# JTAG_Configuration.net
KiCad netlist of a schematic drawn in Altium Designer
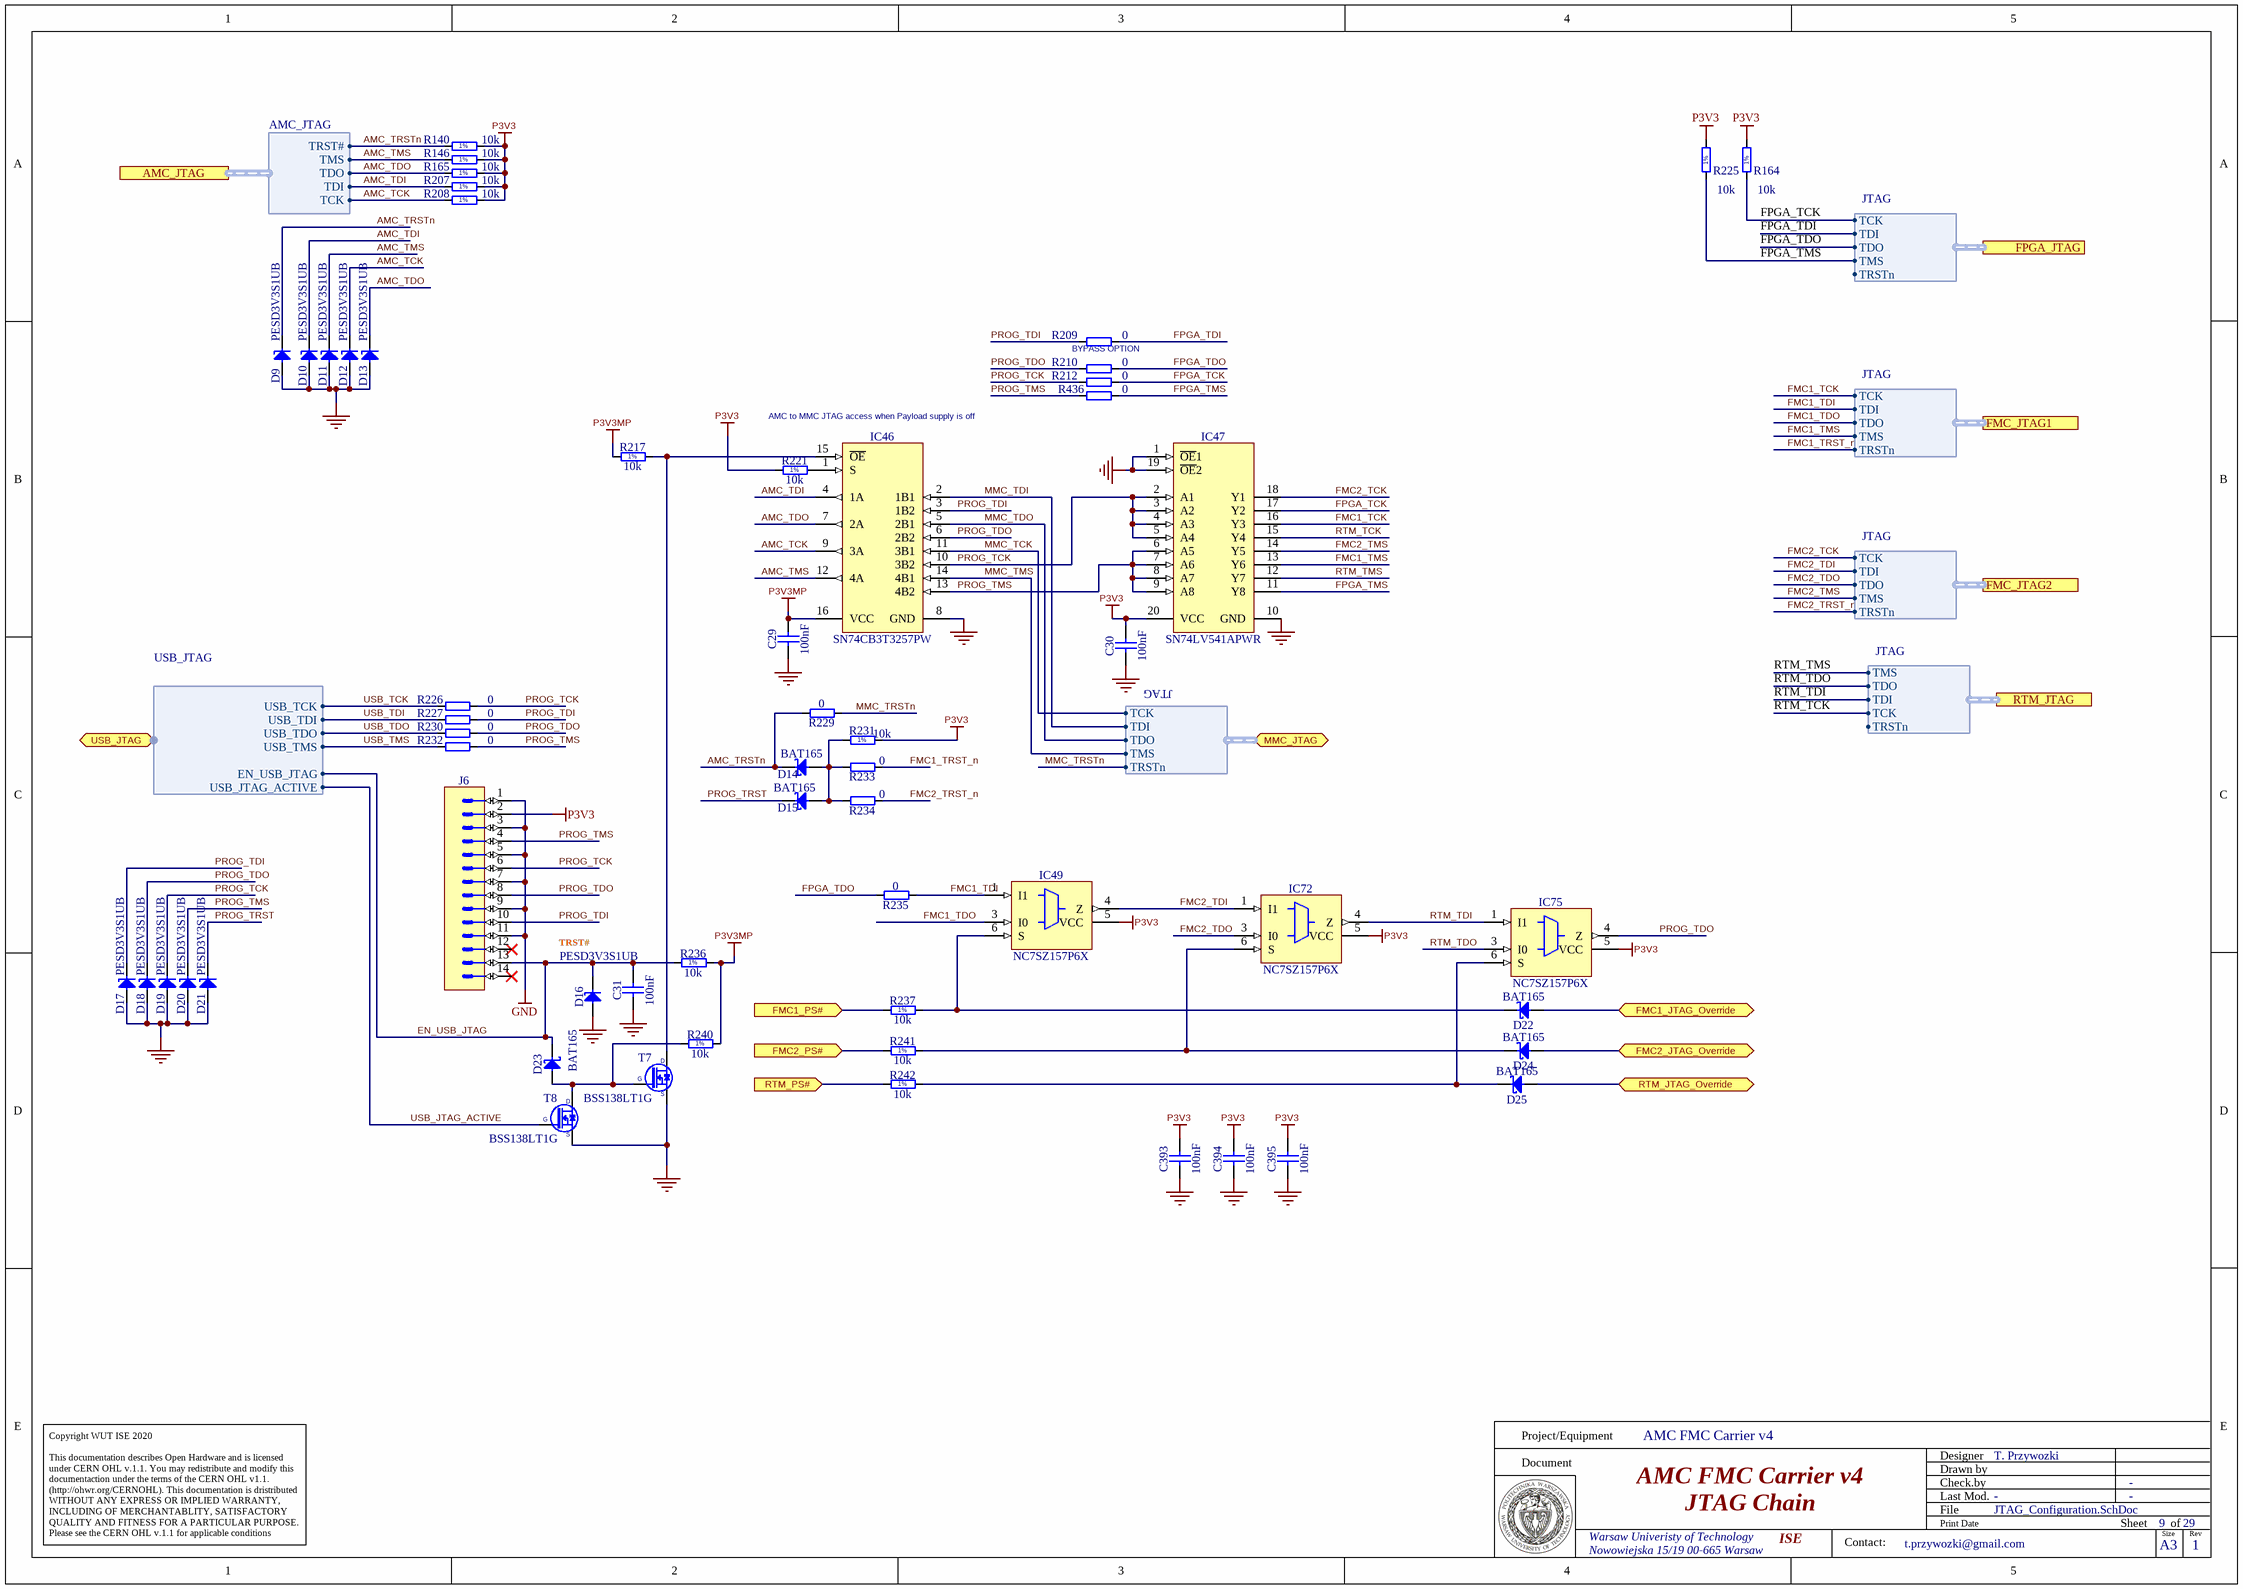
[diagram p0: JTAG_Configuration.SchDoc]

(export (version "E")
  (design (tool "Eeschema 10.0.6"))
  (components
    (comp (ref "C29")
      (value "100nF")
      (footprint "CAPC0603X33N")
      (description "Non-polarised capacitor")
      (fields
        (field (name "MANUFACTURER PART NUMBER") "CC0201_100NF_6.3V_10%_X5R")
        (field (name "MANUFACTURER") "GENERIC")
        (field (name "AUTHOR") "CERN DEM JLC")
      )
      (libsource (lib "Capacitors") (part "Capacitor - non polarized"))
    )
    (comp (ref "C30")
      (value "100nF")
      (footprint "CAPC0603X33N")
      (description "Non-polarised capacitor")
      (fields
        (field (name "MANUFACTURER PART NUMBER") "CC0201_100NF_6.3V_10%_X5R")
        (field (name "MANUFACTURER") "GENERIC")
        (field (name "AUTHOR") "CERN DEM JLC")
      )
      (libsource (lib "Capacitors") (part "Capacitor - non polarized"))
    )
    (comp (ref "C31")
      (value "100nF")
      (footprint "CAPC0603X33N")
      (description "Non-polarised capacitor")
      (fields
        (field (name "MANUFACTURER PART NUMBER") "CC0201_100NF_6.3V_10%_X5R")
        (field (name "MANUFACTURER") "GENERIC")
        (field (name "AUTHOR") "CERN DEM JLC")
      )
      (libsource (lib "Capacitors") (part "Capacitor - non polarized"))
    )
    (comp (ref "C393")
      (value "100nF")
      (footprint "CAPC0603X33N")
      (description "Non-polarised capacitor")
      (fields
        (field (name "MANUFACTURER PART NUMBER") "CC0201_100NF_6.3V_10%_X5R")
        (field (name "MANUFACTURER") "GENERIC")
        (field (name "AUTHOR") "CERN DEM JLC")
      )
      (libsource (lib "Capacitors") (part "Capacitor - non polarized"))
    )
    (comp (ref "C394")
      (value "100nF")
      (footprint "CAPC0603X33N")
      (description "Non-polarised capacitor")
      (fields
        (field (name "MANUFACTURER PART NUMBER") "CC0201_100NF_6.3V_10%_X5R")
        (field (name "MANUFACTURER") "GENERIC")
        (field (name "AUTHOR") "CERN DEM JLC")
      )
      (libsource (lib "Capacitors") (part "Capacitor - non polarized"))
    )
    (comp (ref "C395")
      (value "100nF")
      (footprint "CAPC0603X33N")
      (description "Non-polarised capacitor")
      (fields
        (field (name "MANUFACTURER PART NUMBER") "CC0201_100NF_6.3V_10%_X5R")
        (field (name "MANUFACTURER") "GENERIC")
        (field (name "AUTHOR") "CERN DEM JLC")
      )
      (libsource (lib "Capacitors") (part "Capacitor - non polarized"))
    )
    (comp (ref "D9")
      (value "PESD3V3S1UB")
      (footprint "SODFL1608X65N")
      (description "ESD protection diode")
      (fields
        (field (name "MANUFACTURER") "NXP SEMICONDUCTORS")
        (field (name "VOLTAGE") "3V3")
        (field (name "AUTHOR") "CERN DEM JLC")
      )
      (libsource (lib "ICs And Semiconductors") (part "Diode ESD"))
    )
    (comp (ref "D10")
      (value "PESD3V3S1UB")
      (footprint "SODFL1608X65N")
      (description "ESD protection diode")
      (fields
        (field (name "MANUFACTURER") "NXP SEMICONDUCTORS")
        (field (name "VOLTAGE") "3V3")
        (field (name "AUTHOR") "CERN DEM JLC")
      )
      (libsource (lib "ICs And Semiconductors") (part "Diode ESD"))
    )
    (comp (ref "D11")
      (value "PESD3V3S1UB")
      (footprint "SODFL1608X65N")
      (description "ESD protection diode")
      (fields
        (field (name "MANUFACTURER") "NXP SEMICONDUCTORS")
        (field (name "VOLTAGE") "3V3")
        (field (name "AUTHOR") "CERN DEM JLC")
      )
      (libsource (lib "ICs And Semiconductors") (part "Diode ESD"))
    )
    (comp (ref "D12")
      (value "PESD3V3S1UB")
      (footprint "SODFL1608X65N")
      (description "ESD protection diode")
      (fields
        (field (name "MANUFACTURER") "NXP SEMICONDUCTORS")
        (field (name "VOLTAGE") "3V3")
        (field (name "AUTHOR") "CERN DEM JLC")
      )
      (libsource (lib "ICs And Semiconductors") (part "Diode ESD"))
    )
    (comp (ref "D13")
      (value "PESD3V3S1UB")
      (footprint "SODFL1608X65N")
      (description "ESD protection diode")
      (fields
        (field (name "MANUFACTURER") "NXP SEMICONDUCTORS")
        (field (name "VOLTAGE") "3V3")
        (field (name "AUTHOR") "CERN DEM JLC")
      )
      (libsource (lib "ICs And Semiconductors") (part "Diode ESD"))
    )
    (comp (ref "D14")
      (value "BAT165")
      (footprint "SOD2512X110N")
      (description "Schottky Diode")
      (fields
        (field (name "MANUFACTURER") "INFINEON")
        (field (name "VOLTAGE") "40V")
        (field (name "AUTHOR") "CERN DEM JLC")
      )
      (libsource (lib "ICs And Semiconductors") (part "Diode Schottky"))
    )
    (comp (ref "D15")
      (value "BAT165")
      (footprint "SOD2512X110N")
      (description "Schottky Diode")
      (fields
        (field (name "MANUFACTURER") "INFINEON")
        (field (name "VOLTAGE") "40V")
        (field (name "AUTHOR") "CERN DEM JLC")
      )
      (libsource (lib "ICs And Semiconductors") (part "Diode Schottky"))
    )
    (comp (ref "D16")
      (value "PESD3V3S1UB")
      (footprint "SODFL1608X65N")
      (description "ESD protection diode")
      (fields
        (field (name "MANUFACTURER") "NXP SEMICONDUCTORS")
        (field (name "VOLTAGE") "3V3")
        (field (name "AUTHOR") "CERN DEM JLC")
      )
      (libsource (lib "ICs And Semiconductors") (part "Diode ESD"))
    )
    (comp (ref "D17")
      (value "PESD3V3S1UB")
      (footprint "SODFL1608X65N")
      (description "ESD protection diode")
      (fields
        (field (name "MANUFACTURER") "NXP SEMICONDUCTORS")
        (field (name "VOLTAGE") "3V3")
        (field (name "AUTHOR") "CERN DEM JLC")
      )
      (libsource (lib "ICs And Semiconductors") (part "Diode ESD"))
    )
    (comp (ref "D18")
      (value "PESD3V3S1UB")
      (footprint "SODFL1608X65N")
      (description "ESD protection diode")
      (fields
        (field (name "MANUFACTURER") "NXP SEMICONDUCTORS")
        (field (name "VOLTAGE") "3V3")
        (field (name "AUTHOR") "CERN DEM JLC")
      )
      (libsource (lib "ICs And Semiconductors") (part "Diode ESD"))
    )
    (comp (ref "D19")
      (value "PESD3V3S1UB")
      (footprint "SODFL1608X65N")
      (description "ESD protection diode")
      (fields
        (field (name "MANUFACTURER") "NXP SEMICONDUCTORS")
        (field (name "VOLTAGE") "3V3")
        (field (name "AUTHOR") "CERN DEM JLC")
      )
      (libsource (lib "ICs And Semiconductors") (part "Diode ESD"))
    )
    (comp (ref "D20")
      (value "PESD3V3S1UB")
      (footprint "SODFL1608X65N")
      (description "ESD protection diode")
      (fields
        (field (name "MANUFACTURER") "NXP SEMICONDUCTORS")
        (field (name "VOLTAGE") "3V3")
        (field (name "AUTHOR") "CERN DEM JLC")
      )
      (libsource (lib "ICs And Semiconductors") (part "Diode ESD"))
    )
    (comp (ref "D21")
      (value "PESD3V3S1UB")
      (footprint "SODFL1608X65N")
      (description "ESD protection diode")
      (fields
        (field (name "MANUFACTURER") "NXP SEMICONDUCTORS")
        (field (name "VOLTAGE") "3V3")
        (field (name "AUTHOR") "CERN DEM JLC")
      )
      (libsource (lib "ICs And Semiconductors") (part "Diode ESD"))
    )
    (comp (ref "D22")
      (value "BAT165")
      (footprint "SOD2512X110N")
      (description "Schottky Diode")
      (fields
        (field (name "MANUFACTURER") "INFINEON")
        (field (name "VOLTAGE") "40V")
        (field (name "AUTHOR") "CERN DEM JLC")
      )
      (libsource (lib "ICs And Semiconductors") (part "Diode Schottky"))
    )
    (comp (ref "D23")
      (value "BAT165")
      (footprint "SOD2512X110N")
      (description "Schottky Diode")
      (fields
        (field (name "MANUFACTURER") "INFINEON")
        (field (name "VOLTAGE") "40V")
        (field (name "AUTHOR") "CERN DEM JLC")
      )
      (libsource (lib "ICs And Semiconductors") (part "Diode Schottky"))
    )
    (comp (ref "D24")
      (value "BAT165")
      (footprint "SOD2512X110N")
      (description "Schottky Diode")
      (fields
        (field (name "MANUFACTURER") "INFINEON")
        (field (name "VOLTAGE") "40V")
        (field (name "AUTHOR") "CERN DEM JLC")
      )
      (libsource (lib "ICs And Semiconductors") (part "Diode Schottky"))
    )
    (comp (ref "D25")
      (value "BAT165")
      (footprint "SOD2512X110N")
      (description "Schottky Diode")
      (fields
        (field (name "MANUFACTURER") "INFINEON")
        (field (name "VOLTAGE") "40V")
        (field (name "AUTHOR") "CERN DEM JLC")
      )
      (libsource (lib "ICs And Semiconductors") (part "Diode Schottky"))
    )
    (comp (ref "IC46")
      (value "SN74CB3T3257PW")
      (footprint "SOP65P640X120-16N")
      (description "4-BIT 1-OF-2 FET Multiplexer/Demultiplexer 2.5V/3.3V Low-Voltage Bus Switch 5V Tolerant Shifter")
      (fields (field (name "MANUFACTURER") "TEXAS INSTRUMENTS") (field (name "AUTHOR") "CERN DEM JLC"))
      (libsource (lib "ICs And Semiconductors") (part "743257"))
    )
    (comp (ref "IC47")
      (value "SN74LV541APWR")
      (footprint "SOP65P640X120-20N")
      (description "Octal Buffer/Line Driver with 3-State Outputs")
      (fields (field (name "MANUFACTURER") "TEXAS INSTRUMENTS") (field (name "AUTHOR") "CERN DEM JLC"))
      (libsource (lib "ICs And Semiconductors") (part "74541"))
    )
    (comp (ref "IC49")
      (value "NC7SZ157P6X")
      (footprint "SOT65P210X110-6N")
      (description "TinyLogic® UHS 2-Input Non-Inverting Multiplexer")
      (fields (field (name "MANUFACTURER") "FAIRCHILD SEMICONDUCTOR") (field (name "AUTHOR") "CERN DEM JLC"))
      (libsource (lib "ICs And Semiconductors") (part "NC7SZ157"))
    )
    (comp (ref "IC72")
      (value "NC7SZ157P6X")
      (footprint "SOT65P210X110-6N")
      (description "TinyLogic® UHS 2-Input Non-Inverting Multiplexer")
      (fields (field (name "MANUFACTURER") "FAIRCHILD SEMICONDUCTOR") (field (name "AUTHOR") "CERN DEM JLC"))
      (libsource (lib "ICs And Semiconductors") (part "NC7SZ157"))
    )
    (comp (ref "IC75")
      (value "NC7SZ157P6X")
      (footprint "SOT65P210X110-6N")
      (description "TinyLogic® UHS 2-Input Non-Inverting Multiplexer")
      (fields (field (name "MANUFACTURER") "FAIRCHILD SEMICONDUCTOR") (field (name "AUTHOR") "CERN DEM JLC"))
      (libsource (lib "ICs And Semiconductors") (part "NC7SZ157"))
    )
    (comp (ref "J6")
      (value "Milli-Grid™")
      (footprint "MOLEX_87832-1420")
      (description "Connector 14 Male")
      (fields
        (field (name "PART NUMBER") "MOLEX_87832-1420")
        (field (name "MANUFACTURER") "MOLEX")
        (field (name "AUTHOR") "CERN DEM JLC")
      )
      (libsource (lib "Connectors") (part "Connector 14 Male"))
    )
    (comp (ref "R140")
      (value "10k")
      (footprint "RESC1005X40N")
      (description "Resistor - 1%")
      (fields
        (field (name "MANUFACTURER PART NUMBER") "R0402_10K_1%_0.0625W_100PPM")
        (field (name "MANUFACTURER") "GENERIC")
        (field (name "AUTHOR") "CERN DEM JLC")
      )
      (libsource (lib "Resistors") (part "Resistor - 1%"))
    )
    (comp (ref "R146")
      (value "10k")
      (footprint "RESC1005X40N")
      (description "Resistor - 1%")
      (fields
        (field (name "MANUFACTURER PART NUMBER") "R0402_10K_1%_0.0625W_100PPM")
        (field (name "MANUFACTURER") "GENERIC")
        (field (name "AUTHOR") "CERN DEM JLC")
      )
      (libsource (lib "Resistors") (part "Resistor - 1%"))
    )
    (comp (ref "R164")
      (value "10k")
      (footprint "RESC1005X40N")
      (description "Resistor - 1%")
      (fields
        (field (name "PART NUMBER") "R0402_10K_1%_0.0625W_100PPM")
        (field (name "POWER") "0.0625W")
        (field (name "AUTHOR") "CERN DEM JLC")
      )
      (libsource (lib "Resistors") (part "Resistor - 1%"))
    )
    (comp (ref "R165")
      (value "10k")
      (footprint "RESC1005X40N")
      (description "Resistor - 1%")
      (fields
        (field (name "MANUFACTURER PART NUMBER") "R0402_10K_1%_0.0625W_100PPM")
        (field (name "MANUFACTURER") "GENERIC")
        (field (name "AUTHOR") "CERN DEM JLC")
      )
      (libsource (lib "Resistors") (part "Resistor - 1%"))
    )
    (comp (ref "R207")
      (value "10k")
      (footprint "RESC1005X40N")
      (description "Resistor - 1%")
      (fields
        (field (name "MANUFACTURER PART NUMBER") "R0402_10K_1%_0.0625W_100PPM")
        (field (name "MANUFACTURER") "GENERIC")
        (field (name "AUTHOR") "CERN DEM JLC")
      )
      (libsource (lib "Resistors") (part "Resistor - 1%"))
    )
    (comp (ref "R208")
      (value "10k")
      (footprint "RESC1005X40N")
      (description "Resistor - 1%")
      (fields
        (field (name "MANUFACTURER PART NUMBER") "R0402_10K_1%_0.0625W_100PPM")
        (field (name "MANUFACTURER") "GENERIC")
        (field (name "AUTHOR") "CERN DEM JLC")
      )
      (libsource (lib "Resistors") (part "Resistor - 1%"))
    )
    (comp (ref "R209")
      (value "0")
      (footprint "RESC1005X40N")
      (description "Resistor")
      (fields
        (field (name "MANUFACTURER PART NUMBER") "R0402_0R_JUMPER")
        (field (name "MANUFACTURER") "GENERIC")
        (field (name "AUTHOR") "CERN DEM JLC")
      )
      (libsource (lib "Resistors") (part "Resistor"))
    )
    (comp (ref "R210")
      (value "0")
      (footprint "RESC1005X40N")
      (description "Resistor")
      (fields
        (field (name "MANUFACTURER PART NUMBER") "R0402_0R_JUMPER")
        (field (name "MANUFACTURER") "GENERIC")
        (field (name "AUTHOR") "CERN DEM JLC")
      )
      (libsource (lib "Resistors") (part "Resistor"))
    )
    (comp (ref "R212")
      (value "0")
      (footprint "RESC1005X40N")
      (description "Resistor")
      (fields
        (field (name "MANUFACTURER PART NUMBER") "R0402_0R_JUMPER")
        (field (name "MANUFACTURER") "GENERIC")
        (field (name "AUTHOR") "CERN DEM JLC")
      )
      (libsource (lib "Resistors") (part "Resistor"))
    )
    (comp (ref "R217")
      (value "10k")
      (footprint "RESC1005X40N")
      (description "Resistor - 1%")
      (fields
        (field (name "MANUFACTURER PART NUMBER") "R0402_10K_1%_0.0625W_100PPM")
        (field (name "MANUFACTURER") "GENERIC")
        (field (name "AUTHOR") "CERN DEM JLC")
      )
      (libsource (lib "Resistors") (part "Resistor - 1%"))
    )
    (comp (ref "R221")
      (value "10k")
      (footprint "RESC1005X40N")
      (description "Resistor - 1%")
      (fields
        (field (name "MANUFACTURER PART NUMBER") "R0402_10K_1%_0.0625W_100PPM")
        (field (name "MANUFACTURER") "GENERIC")
        (field (name "AUTHOR") "CERN DEM JLC")
      )
      (libsource (lib "Resistors") (part "Resistor - 1%"))
    )
    (comp (ref "R225")
      (value "10k")
      (footprint "RESC1005X40N")
      (description "Resistor - 1%")
      (fields
        (field (name "PART NUMBER") "R0402_10K_1%_0.0625W_100PPM")
        (field (name "POWER") "0.0625W")
        (field (name "AUTHOR") "CERN DEM JLC")
      )
      (libsource (lib "Resistors") (part "Resistor - 1%"))
    )
    (comp (ref "R226")
      (value "0")
      (footprint "RESC1005X40N")
      (description "Resistor")
      (fields
        (field (name "MANUFACTURER PART NUMBER") "R0402_0R_JUMPER")
        (field (name "MANUFACTURER") "GENERIC")
        (field (name "AUTHOR") "CERN DEM JLC")
      )
      (libsource (lib "Resistors") (part "Resistor"))
    )
    (comp (ref "R227")
      (value "0")
      (footprint "RESC1005X40N")
      (description "Resistor")
      (fields
        (field (name "MANUFACTURER PART NUMBER") "R0402_0R_JUMPER")
        (field (name "MANUFACTURER") "GENERIC")
        (field (name "AUTHOR") "CERN DEM JLC")
      )
      (libsource (lib "Resistors") (part "Resistor"))
    )
    (comp (ref "R229")
      (value "0")
      (footprint "RESC1005X40N")
      (description "Resistor")
      (fields
        (field (name "MANUFACTURER PART NUMBER") "R0402_0R_JUMPER")
        (field (name "MANUFACTURER") "GENERIC")
        (field (name "AUTHOR") "CERN DEM JLC")
      )
      (libsource (lib "Resistors") (part "Resistor"))
    )
    (comp (ref "R230")
      (value "0")
      (footprint "RESC1005X40N")
      (description "Resistor")
      (fields
        (field (name "MANUFACTURER PART NUMBER") "R0402_0R_JUMPER")
        (field (name "MANUFACTURER") "GENERIC")
        (field (name "AUTHOR") "CERN DEM JLC")
      )
      (libsource (lib "Resistors") (part "Resistor"))
    )
    (comp (ref "R231")
      (value "10k")
      (footprint "RESC1005X40N")
      (description "Resistor - 1%")
      (fields
        (field (name "MANUFACTURER PART NUMBER") "R0402_10K_1%_0.0625W_100PPM")
        (field (name "MANUFACTURER") "GENERIC")
        (field (name "AUTHOR") "CERN DEM JLC")
      )
      (libsource (lib "Resistors") (part "Resistor - 1%"))
    )
    (comp (ref "R232")
      (value "0")
      (footprint "RESC1005X40N")
      (description "Resistor")
      (fields
        (field (name "MANUFACTURER PART NUMBER") "R0402_0R_JUMPER")
        (field (name "MANUFACTURER") "GENERIC")
        (field (name "AUTHOR") "CERN DEM JLC")
      )
      (libsource (lib "Resistors") (part "Resistor"))
    )
    (comp (ref "R233")
      (value "0")
      (footprint "RESC1005X40N")
      (description "Resistor")
      (fields
        (field (name "MANUFACTURER PART NUMBER") "R0402_0R_JUMPER")
        (field (name "MANUFACTURER") "GENERIC")
        (field (name "AUTHOR") "CERN DEM JLC")
      )
      (libsource (lib "Resistors") (part "Resistor"))
    )
    (comp (ref "R234")
      (value "0")
      (footprint "RESC1005X40N")
      (description "Resistor")
      (fields
        (field (name "MANUFACTURER PART NUMBER") "R0402_0R_JUMPER")
        (field (name "MANUFACTURER") "GENERIC")
        (field (name "AUTHOR") "CERN DEM JLC")
      )
      (libsource (lib "Resistors") (part "Resistor"))
    )
    (comp (ref "R235")
      (value "0")
      (footprint "RESC1005X40N")
      (description "Resistor")
      (fields
        (field (name "MANUFACTURER PART NUMBER") "R0402_0R_JUMPER")
        (field (name "MANUFACTURER") "GENERIC")
        (field (name "AUTHOR") "CERN DEM JLC")
      )
      (libsource (lib "Resistors") (part "Resistor"))
    )
    (comp (ref "R236")
      (value "10k")
      (footprint "RESC1005X40N")
      (description "Resistor - 1%")
      (fields
        (field (name "MANUFACTURER PART NUMBER") "R0402_10K_1%_0.0625W_100PPM")
        (field (name "MANUFACTURER") "GENERIC")
        (field (name "AUTHOR") "CERN DEM JLC")
      )
      (libsource (lib "Resistors") (part "Resistor - 1%"))
    )
    (comp (ref "R237")
      (value "10k")
      (footprint "RESC1005X40N")
      (description "Resistor - 1%")
      (fields
        (field (name "MANUFACTURER PART NUMBER") "R0402_10K_1%_0.0625W_100PPM")
        (field (name "MANUFACTURER") "GENERIC")
        (field (name "AUTHOR") "CERN DEM JLC")
      )
      (libsource (lib "Resistors") (part "Resistor - 1%"))
    )
    (comp (ref "R240")
      (value "10k")
      (footprint "RESC1005X40N")
      (description "Resistor - 1%")
      (fields
        (field (name "MANUFACTURER PART NUMBER") "R0402_10K_1%_0.0625W_100PPM")
        (field (name "MANUFACTURER") "GENERIC")
        (field (name "AUTHOR") "CERN DEM JLC")
      )
      (libsource (lib "Resistors") (part "Resistor - 1%"))
    )
    (comp (ref "R241")
      (value "10k")
      (footprint "RESC1005X40N")
      (description "Resistor - 1%")
      (fields
        (field (name "MANUFACTURER PART NUMBER") "R0402_10K_1%_0.0625W_100PPM")
        (field (name "MANUFACTURER") "GENERIC")
        (field (name "AUTHOR") "CERN DEM JLC")
      )
      (libsource (lib "Resistors") (part "Resistor - 1%"))
    )
    (comp (ref "R242")
      (value "10k")
      (footprint "RESC1005X40N")
      (description "Resistor - 1%")
      (fields
        (field (name "MANUFACTURER PART NUMBER") "R0402_10K_1%_0.0625W_100PPM")
        (field (name "MANUFACTURER") "GENERIC")
        (field (name "AUTHOR") "CERN DEM JLC")
      )
      (libsource (lib "Resistors") (part "Resistor - 1%"))
    )
    (comp (ref "R436")
      (value "0")
      (footprint "RESC1005X40N")
      (description "Resistor")
      (fields
        (field (name "MANUFACTURER PART NUMBER") "R0402_0R_JUMPER")
        (field (name "MANUFACTURER") "GENERIC")
        (field (name "AUTHOR") "CERN DEM JLC")
      )
      (libsource (lib "Resistors") (part "Resistor"))
    )
    (comp (ref "T7")
      (value "BSS138LT1G")
      (footprint "SOT95P240X110-3N")
      (description "N-CHANNEL MOSFET WITH DIODE")
      (fields (field (name "MANUFACTURER") "ON SEMICONDUCTOR") (field (name "AUTHOR") "CERN DEM JLC"))
      (libsource (lib "ICs And Semiconductors") (part "N-MOSFET-D 1G 2S 3D"))
    )
    (comp (ref "T8")
      (value "BSS138LT1G")
      (footprint "SOT95P240X110-3N")
      (description "N-CHANNEL MOSFET WITH DIODE")
      (fields (field (name "MANUFACTURER") "ON SEMICONDUCTOR") (field (name "AUTHOR") "CERN DEM JLC"))
      (libsource (lib "ICs And Semiconductors") (part "N-MOSFET-D 1G 2S 3D"))
    )
  )
  (nets
    (net (code "4") (name "/AMC_TCK") (class "Default")
      (node (ref "D12") (pin "1") (pinfunction "C_1") (pintype "passive"))
      (node (ref "IC46") (pin "9") (pinfunction "3A_9") (pintype "output"))
      (node (ref "R208") (pin "2") (pinfunction "2_2") (pintype "passive"))
    )
    (net (code "5") (name "/AMC_TDI") (class "Default")
      (node (ref "D10") (pin "1") (pinfunction "C_1") (pintype "passive"))
      (node (ref "IC46") (pin "4") (pinfunction "1A_4") (pintype "output"))
      (node (ref "R207") (pin "2") (pinfunction "2_2") (pintype "passive"))
    )
    (net (code "6") (name "/AMC_TDO") (class "Default")
      (node (ref "D13") (pin "1") (pinfunction "C_1") (pintype "passive"))
      (node (ref "IC46") (pin "7") (pinfunction "2A_7") (pintype "output"))
      (node (ref "R165") (pin "2") (pinfunction "2_2") (pintype "passive"))
    )
    (net (code "7") (name "/AMC_TMS") (class "Default")
      (node (ref "D11") (pin "1") (pinfunction "C_1") (pintype "passive"))
      (node (ref "IC46") (pin "12") (pinfunction "4A_12") (pintype "output"))
      (node (ref "R146") (pin "2") (pinfunction "2_2") (pintype "passive"))
    )
    (net (code "8") (name "/AMC_TRSTn") (class "Default")
      (node (ref "D14") (pin "1") (pinfunction "C_1") (pintype "passive"))
      (node (ref "D9") (pin "1") (pinfunction "C_1") (pintype "passive"))
      (node (ref "R140") (pin "2") (pinfunction "2_2") (pintype "passive"))
      (node (ref "R229") (pin "2") (pinfunction "2_2") (pintype "passive"))
    )
    (net (code "9") (name "/EN_USB_JTAG") (class "Default")
      (node (ref "C31") (pin "2") (pinfunction "2_2") (pintype "passive"))
      (node (ref "D16") (pin "1") (pinfunction "C_1") (pintype "passive"))
      (node (ref "D23") (pin "1") (pinfunction "C_1") (pintype "passive"))
      (node (ref "J6") (pin "13") (pinfunction "13_13") (pintype "bidirectional"))
      (node (ref "R236") (pin "1") (pinfunction "1_1") (pintype "passive"))
    )
    (net (code "10") (name "/FMC1_JTAG_Override") (class "Default")
      (node (ref "D22") (pin "2") (pinfunction "A_2") (pintype "passive"))
    )
    (net (code "11") (name "/FMC1_PS#") (class "Default")
      (node (ref "R237") (pin "2") (pinfunction "2_2") (pintype "passive"))
    )
    (net (code "12") (name "/FMC1_TCK") (class "Default")
      (node (ref "IC47") (pin "16") (pinfunction "Y3_16") (pintype "tri_state"))
    )
    (net (code "13") (name "/FMC1_TDI") (class "Default")
      (node (ref "IC49") (pin "1") (pinfunction "I1_1") (pintype "input"))
      (node (ref "R235") (pin "1") (pinfunction "1_1") (pintype "passive"))
    )
    (net (code "14") (name "/FMC1_TDO") (class "Default")
      (node (ref "IC49") (pin "3") (pinfunction "I0_3") (pintype "input"))
    )
    (net (code "15") (name "/FMC1_TMS") (class "Default")
      (node (ref "IC47") (pin "13") (pinfunction "Y6_13") (pintype "tri_state"))
    )
    (net (code "16") (name "/FMC1_TRST_n") (class "Default")
      (node (ref "R233") (pin "1") (pinfunction "1_1") (pintype "passive"))
    )
    (net (code "17") (name "/FMC2_JTAG_Override") (class "Default")
      (node (ref "D24") (pin "2") (pinfunction "A_2") (pintype "passive"))
    )
    (net (code "18") (name "/FMC2_PS#") (class "Default")
      (node (ref "R241") (pin "2") (pinfunction "2_2") (pintype "passive"))
    )
    (net (code "19") (name "/FMC2_TCK") (class "Default")
      (node (ref "IC47") (pin "18") (pinfunction "Y1_18") (pintype "tri_state"))
    )
    (net (code "20") (name "/FMC2_TDI") (class "Default")
      (node (ref "IC49") (pin "4") (pinfunction "Z_4") (pintype "output"))
      (node (ref "IC72") (pin "1") (pinfunction "I1_1") (pintype "input"))
    )
    (net (code "21") (name "/FMC2_TDO") (class "Default")
      (node (ref "IC72") (pin "3") (pinfunction "I0_3") (pintype "input"))
    )
    (net (code "22") (name "/FMC2_TMS") (class "Default")
      (node (ref "IC47") (pin "14") (pinfunction "Y5_14") (pintype "tri_state"))
    )
    (net (code "23") (name "/FMC2_TRST_n") (class "Default")
      (node (ref "R234") (pin "1") (pinfunction "1_1") (pintype "passive"))
    )
    (net (code "24") (name "/FPGA_TCK") (class "Default")
      (node (ref "IC47") (pin "17") (pinfunction "Y2_17") (pintype "tri_state"))
      (node (ref "R164") (pin "1") (pinfunction "1_1") (pintype "passive"))
      (node (ref "R212") (pin "1") (pinfunction "1_1") (pintype "passive"))
    )
    (net (code "25") (name "/FPGA_TDI") (class "Default")
      (node (ref "R209") (pin "1") (pinfunction "1_1") (pintype "passive"))
    )
    (net (code "26") (name "/FPGA_TDO") (class "Default")
      (node (ref "R210") (pin "1") (pinfunction "1_1") (pintype "passive"))
      (node (ref "R235") (pin "2") (pinfunction "2_2") (pintype "passive"))
    )
    (net (code "27") (name "/FPGA_TMS") (class "Default")
      (node (ref "IC47") (pin "11") (pinfunction "Y8_11") (pintype "tri_state"))
      (node (ref "R225") (pin "1") (pinfunction "1_1") (pintype "passive"))
      (node (ref "R436") (pin "1") (pinfunction "1_1") (pintype "passive"))
    )
    (net (code "28") (name "/MMC_TCK") (class "Default")
      (node (ref "IC46") (pin "11") (pinfunction "3B1_11") (pintype "input"))
    )
    (net (code "29") (name "/MMC_TDI") (class "Default")
      (node (ref "IC46") (pin "2") (pinfunction "1B1_2") (pintype "input"))
    )
    (net (code "30") (name "/MMC_TDO") (class "Default")
      (node (ref "IC46") (pin "5") (pinfunction "2B1_5") (pintype "input"))
    )
    (net (code "31") (name "/MMC_TMS") (class "Default")
      (node (ref "IC46") (pin "14") (pinfunction "4B1_14") (pintype "input"))
    )
    (net (code "32") (name "/MMC_TRSTn") (class "Default")
      (node (ref "R229") (pin "1") (pinfunction "1_1") (pintype "passive"))
    )
    (net (code "33") (name "/PROG_TCK") (class "Default")
      (node (ref "D19") (pin "1") (pinfunction "C_1") (pintype "passive"))
      (node (ref "IC46") (pin "10") (pinfunction "3B2_10") (pintype "input"))
      (node (ref "IC47") (pin "2") (pinfunction "A1_2") (pintype "input"))
      (node (ref "IC47") (pin "3") (pinfunction "A2_3") (pintype "input"))
      (node (ref "IC47") (pin "4") (pinfunction "A3_4") (pintype "input"))
      (node (ref "IC47") (pin "5") (pinfunction "A4_5") (pintype "input"))
      (node (ref "J6") (pin "6") (pinfunction "6_6") (pintype "bidirectional"))
      (node (ref "R212") (pin "2") (pinfunction "2_2") (pintype "passive"))
      (node (ref "R226") (pin "1") (pinfunction "1_1") (pintype "passive"))
    )
    (net (code "34") (name "/PROG_TDI") (class "Default")
      (node (ref "D17") (pin "1") (pinfunction "C_1") (pintype "passive"))
      (node (ref "IC46") (pin "3") (pinfunction "1B2_3") (pintype "input"))
      (node (ref "J6") (pin "10") (pinfunction "10_10") (pintype "bidirectional"))
      (node (ref "R209") (pin "2") (pinfunction "2_2") (pintype "passive"))
      (node (ref "R227") (pin "1") (pinfunction "1_1") (pintype "passive"))
    )
    (net (code "35") (name "/PROG_TDO") (class "Default")
      (node (ref "D18") (pin "1") (pinfunction "C_1") (pintype "passive"))
      (node (ref "IC46") (pin "6") (pinfunction "2B2_6") (pintype "input"))
      (node (ref "IC75") (pin "4") (pinfunction "Z_4") (pintype "output"))
      (node (ref "J6") (pin "8") (pinfunction "8_8") (pintype "bidirectional"))
      (node (ref "R210") (pin "2") (pinfunction "2_2") (pintype "passive"))
      (node (ref "R230") (pin "1") (pinfunction "1_1") (pintype "passive"))
    )
    (net (code "36") (name "/PROG_TMS") (class "Default")
      (node (ref "D20") (pin "1") (pinfunction "C_1") (pintype "passive"))
      (node (ref "IC46") (pin "13") (pinfunction "4B2_13") (pintype "input"))
      (node (ref "IC47") (pin "6") (pinfunction "A5_6") (pintype "input"))
      (node (ref "IC47") (pin "7") (pinfunction "A6_7") (pintype "input"))
      (node (ref "IC47") (pin "8") (pinfunction "A7_8") (pintype "input"))
      (node (ref "IC47") (pin "9") (pinfunction "A8_9") (pintype "input"))
      (node (ref "J6") (pin "4") (pinfunction "4_4") (pintype "bidirectional"))
      (node (ref "R232") (pin "1") (pinfunction "1_1") (pintype "passive"))
      (node (ref "R436") (pin "2") (pinfunction "2_2") (pintype "passive"))
    )
    (net (code "37") (name "/PROG_TRST") (class "Default")
      (node (ref "D15") (pin "1") (pinfunction "C_1") (pintype "passive"))
      (node (ref "D21") (pin "1") (pinfunction "C_1") (pintype "passive"))
    )
    (net (code "38") (name "/RTM_JTAG_Override") (class "Default")
      (node (ref "D25") (pin "2") (pinfunction "A_2") (pintype "passive"))
    )
    (net (code "39") (name "/RTM_PS#") (class "Default")
      (node (ref "R242") (pin "2") (pinfunction "2_2") (pintype "passive"))
    )
    (net (code "40") (name "/RTM_TCK") (class "Default")
      (node (ref "IC47") (pin "15") (pinfunction "Y4_15") (pintype "tri_state"))
    )
    (net (code "41") (name "/RTM_TDI") (class "Default")
      (node (ref "IC72") (pin "4") (pinfunction "Z_4") (pintype "output"))
      (node (ref "IC75") (pin "1") (pinfunction "I1_1") (pintype "input"))
    )
    (net (code "42") (name "/RTM_TDO") (class "Default")
      (node (ref "IC75") (pin "3") (pinfunction "I0_3") (pintype "input"))
    )
    (net (code "43") (name "/RTM_TMS") (class "Default")
      (node (ref "IC47") (pin "12") (pinfunction "Y7_12") (pintype "tri_state"))
    )
    (net (code "44") (name "/USB_JTAG_ACTIVE") (class "Default")
      (node (ref "T8") (pin "1") (pinfunction "G_1") (pintype "passive"))
    )
    (net (code "45") (name "/USB_TCK") (class "Default")
      (node (ref "R226") (pin "2") (pinfunction "2_2") (pintype "passive"))
    )
    (net (code "46") (name "/USB_TDI") (class "Default")
      (node (ref "R227") (pin "2") (pinfunction "2_2") (pintype "passive"))
    )
    (net (code "47") (name "/USB_TDO") (class "Default")
      (node (ref "R230") (pin "2") (pinfunction "2_2") (pintype "passive"))
    )
    (net (code "48") (name "/USB_TMS") (class "Default")
      (node (ref "R232") (pin "2") (pinfunction "2_2") (pintype "passive"))
    )
    (net (code "52") (name "GND") (class "Default")
      (node (ref "C29") (pin "1") (pinfunction "1_1") (pintype "passive"))
      (node (ref "C30") (pin "1") (pinfunction "1_1") (pintype "passive"))
      (node (ref "C31") (pin "1") (pinfunction "1_1") (pintype "passive"))
      (node (ref "C393") (pin "1") (pinfunction "1_1") (pintype "passive"))
      (node (ref "C394") (pin "1") (pinfunction "1_1") (pintype "passive"))
      (node (ref "C395") (pin "1") (pinfunction "1_1") (pintype "passive"))
      (node (ref "D10") (pin "2") (pinfunction "A_2") (pintype "passive"))
      (node (ref "D11") (pin "2") (pinfunction "A_2") (pintype "passive"))
      (node (ref "D12") (pin "2") (pinfunction "A_2") (pintype "passive"))
      (node (ref "D13") (pin "2") (pinfunction "A_2") (pintype "passive"))
      (node (ref "D16") (pin "2") (pinfunction "A_2") (pintype "passive"))
      (node (ref "D17") (pin "2") (pinfunction "A_2") (pintype "passive"))
      (node (ref "D18") (pin "2") (pinfunction "A_2") (pintype "passive"))
      (node (ref "D19") (pin "2") (pinfunction "A_2") (pintype "passive"))
      (node (ref "D20") (pin "2") (pinfunction "A_2") (pintype "passive"))
      (node (ref "D21") (pin "2") (pinfunction "A_2") (pintype "passive"))
      (node (ref "D9") (pin "2") (pinfunction "A_2") (pintype "passive"))
      (node (ref "IC46") (pin "8") (pinfunction "GND_8") (pintype "power_in"))
      (node (ref "IC47") (pin "1") (pinfunction "~{OE}1_1") (pintype "input"))
      (node (ref "IC47") (pin "10") (pinfunction "GND_10") (pintype "power_in"))
      (node (ref "IC47") (pin "19") (pinfunction "~{OE}2_19") (pintype "input"))
      (node (ref "IC49") (pin "2") (pinfunction "GND_2") (pintype "power_in"))
      (node (ref "IC72") (pin "2") (pinfunction "GND_2") (pintype "power_in"))
      (node (ref "IC75") (pin "2") (pinfunction "GND_2") (pintype "power_in"))
      (node (ref "J6") (pin "1") (pinfunction "1_1") (pintype "bidirectional"))
      (node (ref "J6") (pin "11") (pinfunction "11_11") (pintype "bidirectional"))
      (node (ref "J6") (pin "3") (pinfunction "3_3") (pintype "bidirectional"))
      (node (ref "J6") (pin "5") (pinfunction "5_5") (pintype "bidirectional"))
      (node (ref "J6") (pin "7") (pinfunction "7_7") (pintype "bidirectional"))
      (node (ref "J6") (pin "9") (pinfunction "9_9") (pintype "bidirectional"))
      (node (ref "T7") (pin "2") (pinfunction "S_2") (pintype "passive"))
      (node (ref "T8") (pin "2") (pinfunction "S_2") (pintype "passive"))
    )
    (net (code "53") (name "Net-(D14-A)") (class "Default")
      (node (ref "D14") (pin "2") (pinfunction "A_2") (pintype "passive"))
      (node (ref "D15") (pin "2") (pinfunction "A_2") (pintype "passive"))
      (node (ref "R231") (pin "2") (pinfunction "2_2") (pintype "passive"))
      (node (ref "R233") (pin "2") (pinfunction "2_2") (pintype "passive"))
      (node (ref "R234") (pin "2") (pinfunction "2_2") (pintype "passive"))
    )
    (net (code "54") (name "Net-(D22-C)") (class "Default")
      (node (ref "D22") (pin "1") (pinfunction "C_1") (pintype "passive"))
      (node (ref "IC49") (pin "6") (pinfunction "S_6") (pintype "input"))
      (node (ref "R237") (pin "1") (pinfunction "1_1") (pintype "passive"))
    )
    (net (code "55") (name "Net-(D23-A)") (class "Default")
      (node (ref "D23") (pin "2") (pinfunction "A_2") (pintype "passive"))
      (node (ref "R240") (pin "1") (pinfunction "1_1") (pintype "passive"))
      (node (ref "T7") (pin "1") (pinfunction "G_1") (pintype "passive"))
      (node (ref "T8") (pin "3") (pinfunction "D_3") (pintype "passive"))
    )
    (net (code "56") (name "Net-(D24-C)") (class "Default")
      (node (ref "D24") (pin "1") (pinfunction "C_1") (pintype "passive"))
      (node (ref "IC72") (pin "6") (pinfunction "S_6") (pintype "input"))
      (node (ref "R241") (pin "1") (pinfunction "1_1") (pintype "passive"))
    )
    (net (code "57") (name "Net-(D25-C)") (class "Default")
      (node (ref "D25") (pin "1") (pinfunction "C_1") (pintype "passive"))
      (node (ref "IC75") (pin "6") (pinfunction "S_6") (pintype "input"))
      (node (ref "R242") (pin "1") (pinfunction "1_1") (pintype "passive"))
    )
    (net (code "58") (name "Net-(IC46-S)") (class "Default")
      (node (ref "IC46") (pin "1") (pinfunction "S_1") (pintype "input"))
      (node (ref "R221") (pin "1") (pinfunction "1_1") (pintype "passive"))
    )
    (net (code "59") (name "Net-(IC46-~{OE})") (class "Default")
      (node (ref "IC46") (pin "15") (pinfunction "~{OE}_15") (pintype "input"))
      (node (ref "R217") (pin "1") (pinfunction "1_1") (pintype "passive"))
      (node (ref "T7") (pin "3") (pinfunction "D_3") (pintype "passive"))
    )
    (net (code "60") (name "P3V3") (class "Default")
      (node (ref "C30") (pin "2") (pinfunction "2_2") (pintype "passive"))
      (node (ref "C393") (pin "2") (pinfunction "2_2") (pintype "passive"))
      (node (ref "C394") (pin "2") (pinfunction "2_2") (pintype "passive"))
      (node (ref "C395") (pin "2") (pinfunction "2_2") (pintype "passive"))
      (node (ref "IC47") (pin "20") (pinfunction "VCC_20") (pintype "power_in"))
      (node (ref "IC49") (pin "5") (pinfunction "VCC_5") (pintype "power_in"))
      (node (ref "IC72") (pin "5") (pinfunction "VCC_5") (pintype "power_in"))
      (node (ref "IC75") (pin "5") (pinfunction "VCC_5") (pintype "power_in"))
      (node (ref "J6") (pin "2") (pinfunction "2_2") (pintype "bidirectional"))
      (node (ref "R140") (pin "1") (pinfunction "1_1") (pintype "passive"))
      (node (ref "R146") (pin "1") (pinfunction "1_1") (pintype "passive"))
      (node (ref "R164") (pin "2") (pinfunction "2_2") (pintype "passive"))
      (node (ref "R165") (pin "1") (pinfunction "1_1") (pintype "passive"))
      (node (ref "R207") (pin "1") (pinfunction "1_1") (pintype "passive"))
      (node (ref "R208") (pin "1") (pinfunction "1_1") (pintype "passive"))
      (node (ref "R221") (pin "2") (pinfunction "2_2") (pintype "passive"))
      (node (ref "R225") (pin "2") (pinfunction "2_2") (pintype "passive"))
      (node (ref "R231") (pin "1") (pinfunction "1_1") (pintype "passive"))
    )
    (net (code "61") (name "P3V3MP") (class "Default")
      (node (ref "C29") (pin "2") (pinfunction "2_2") (pintype "passive"))
      (node (ref "IC46") (pin "16") (pinfunction "VCC_16") (pintype "power_in"))
      (node (ref "R217") (pin "2") (pinfunction "2_2") (pintype "passive"))
      (node (ref "R236") (pin "2") (pinfunction "2_2") (pintype "passive"))
      (node (ref "R240") (pin "2") (pinfunction "2_2") (pintype "passive"))
    )
    (net (code "62") (name "unconnected-(J6-Pad12)") (class "Default")
      (node (ref "J6") (pin "12") (pinfunction "12_12") (pintype "bidirectional+no_connect"))
    )
    (net (code "63") (name "unconnected-(J6-Pad14)") (class "Default")
      (node (ref "J6") (pin "14") (pinfunction "14_14") (pintype "bidirectional+no_connect"))
    )
  )
)
